# POWER.net
KiCad netlist of a schematic drawn in Altium Designer
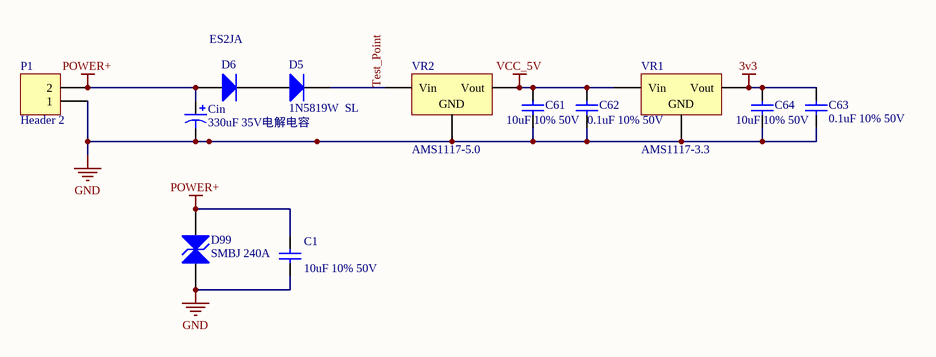
[diagram p0: POWER.SchDoc]

(export (version "E")
  (design (tool "Eeschema 10.0.6"))
  (components
    (comp (ref "C1")
      (value "10uF 10% 50V")
      (footprint "0805_C")
      (description "Capacitor (Semiconductor SIM Model)")
      (fields (field (name "PUBLISHER") "Altium Limited"))
      (libsource (lib "Miscellaneous Devices") (part "Cap Semi"))
    )
    (comp (ref "C61")
      (value "10uF 10% 50V")
      (footprint "0805_C")
      (description "Capacitor (Semiconductor SIM Model)")
      (fields (field (name "PUBLISHER") "Altium Limited"))
      (libsource (lib "Miscellaneous Devices") (part "Cap Semi"))
    )
    (comp (ref "C62")
      (value "0.1uF 10% 50V")
      (footprint "0603_C")
      (description "Capacitor (Semiconductor SIM Model)")
      (fields (field (name "PUBLISHER") "Altium Limited"))
      (libsource (lib "Miscellaneous Devices") (part "Cap Semi"))
    )
    (comp (ref "C63")
      (value "0.1uF 10% 50V")
      (footprint "0603_C")
      (description "Capacitor (Semiconductor SIM Model)")
      (fields (field (name "PUBLISHER") "Altium Limited"))
      (libsource (lib "Miscellaneous Devices") (part "Cap Semi"))
    )
    (comp (ref "C64")
      (value "10uF 10% 50V")
      (footprint "0805_C")
      (description "Capacitor (Semiconductor SIM Model)")
      (fields (field (name "PUBLISHER") "Altium Limited"))
      (libsource (lib "Miscellaneous Devices") (part "Cap Semi"))
    )
    (comp (ref "Cin")
      (value "330uF 35V电解电容")
      (footprint "330uf/35V")
      (description "Polarized Capacitor (Radial)")
      (fields (field (name "PUBLISHER") "Altium Limited"))
      (libsource (lib "Miscellaneous Devices") (part "Cap Pol1"))
    )
    (comp (ref "D5")
      (value "1N5819W  SL")
      (footprint "SOD-123")
      (description "肖特基二极管")
      (libsource (lib "Diode") (part "SOD-123 B5819W  SL"))
    )
    (comp (ref "D6")
      (value "ES2JA")
      (footprint "SMA(DO-214AC)_S1")
      (description "二极管")
      (libsource (lib "Diode") (part "SMA(DO-214AC) M7"))
    )
    (comp (ref "D99")
      (value "SMBJ 240A")
      (footprint "SMB(DO-214AA)_S1")
      (description "TVS")
      (libsource (lib "Diode") (part "SMB/DO-214AA P6SMB6.8CA"))
    )
    (comp (ref "P1")
      (value "Header 2")
      (footprint "2星座子")
      (description "Header, 2-Pin")
      (fields (field (name "PUBLISHER") "Altium Limited"))
      (libsource (lib "Miscellaneous Connectors") (part "Header 2"))
    )
    (comp (ref "VR1")
      (value "AMS1117-3.3")
      (footprint "SOT-223")
      (description "低压差线性稳压(LDO)")
      (libsource (lib "LDO") (part "SOT-223 AMS1117-5.0"))
    )
    (comp (ref "VR2")
      (value "AMS1117-5.0")
      (footprint "SOT-223")
      (description "低压差线性稳压(LDO)")
      (libsource (lib "LDO") (part "SOT-223 AMS1117-5.0"))
    )
  )
  (nets
    (net (code "1") (name "/Test_Point") (class "Default")
      (node (ref "D5") (pin "2") (pinfunction "K_2") (pintype "passive"))
      (node (ref "VR2") (pin "3") (pinfunction "Vin_3") (pintype "passive"))
    )
    (net (code "2") (name "3v3") (class "Default")
      (node (ref "C63") (pin "2") (pinfunction "2_2") (pintype "passive"))
      (node (ref "C64") (pin "1") (pinfunction "1_1") (pintype "passive"))
      (node (ref "VR1") (pin "2") (pinfunction "Vout_2") (pintype "passive"))
    )
    (net (code "3") (name "GND") (class "Default")
      (node (ref "C1") (pin "2") (pinfunction "2_2") (pintype "passive"))
      (node (ref "C61") (pin "2") (pinfunction "2_2") (pintype "passive"))
      (node (ref "C62") (pin "1") (pinfunction "1_1") (pintype "passive"))
      (node (ref "C63") (pin "1") (pinfunction "1_1") (pintype "passive"))
      (node (ref "C64") (pin "2") (pinfunction "2_2") (pintype "passive"))
      (node (ref "Cin") (pin "2") (pinfunction "2_2") (pintype "passive"))
      (node (ref "D99") (pin "1") (pinfunction "A_1") (pintype "passive"))
      (node (ref "P1") (pin "1") (pinfunction "1_1") (pintype "passive"))
      (node (ref "VR1") (pin "1") (pinfunction "GND_1") (pintype "passive"))
      (node (ref "VR2") (pin "1") (pinfunction "GND_1") (pintype "passive"))
    )
    (net (code "4") (name "Net-(D5-A)") (class "Default")
      (node (ref "D5") (pin "1") (pinfunction "A_1") (pintype "passive"))
      (node (ref "D6") (pin "2") (pinfunction "K_2") (pintype "passive"))
    )
    (net (code "5") (name "POWER+") (class "Default")
      (node (ref "C1") (pin "1") (pinfunction "1_1") (pintype "passive"))
      (node (ref "Cin") (pin "1") (pinfunction "1_1") (pintype "passive"))
      (node (ref "D6") (pin "1") (pinfunction "A_1") (pintype "passive"))
      (node (ref "D99") (pin "2") (pinfunction "K_2") (pintype "passive"))
      (node (ref "P1") (pin "2") (pinfunction "2_2") (pintype "passive"))
    )
    (net (code "6") (name "VCC_5V") (class "Default")
      (node (ref "C61") (pin "1") (pinfunction "1_1") (pintype "passive"))
      (node (ref "C62") (pin "2") (pinfunction "2_2") (pintype "passive"))
      (node (ref "VR1") (pin "3") (pinfunction "Vin_3") (pintype "passive"))
      (node (ref "VR2") (pin "2") (pinfunction "Vout_2") (pintype "passive"))
    )
  )
)
